# design.net
KiCad netlist of a schematic drawn in Altium Designer
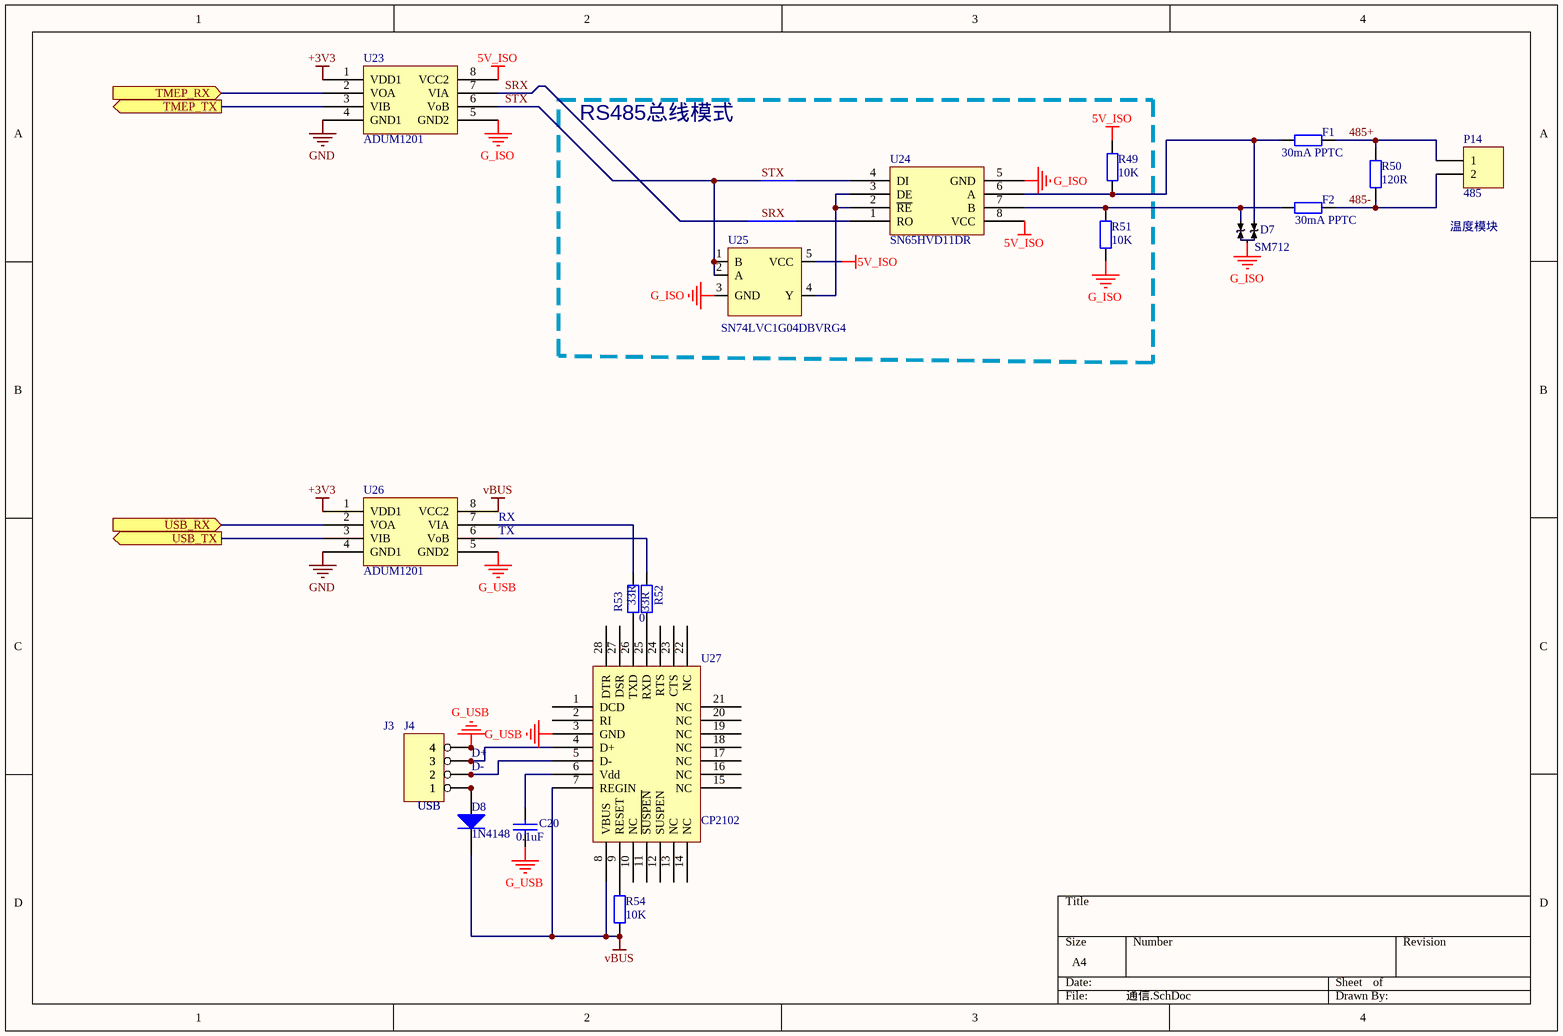
[diagram p0: 通信.SchDoc]

(export (version "E")
  (design (tool "Eeschema 10.0.6"))
  (components
    (comp (ref "C20")
      (value "0.1uF")
      (footprint "1608C")
      (description "Capacitor")
      (libsource (lib "*") (part "CAP"))
    )
    (comp (ref "D7") (value "SM712") (footprint "sot-23") (libsource (lib "Schlib1") (part "NUP2105L-D")))
    (comp (ref "D8")
      (value "1N4148")
      (footprint "SOD-123")
      (description "Default Diode")
      (fields (field (name "PUBLISHER") "Altium Limited"))
      (libsource (lib "*") (part "Diode"))
    )
    (comp (ref "F1")
      (value "30mA PPTC")
      (footprint "1608")
      (description "Resistor")
      (fields (field (name "PUBLISHER") "Altium Limited"))
      (libsource (lib "*") (part "Res2"))
    )
    (comp (ref "F2")
      (value "30mA PPTC")
      (footprint "1608")
      (description "Resistor")
      (fields (field (name "PUBLISHER") "Altium Limited"))
      (libsource (lib "*") (part "Res2"))
    )
    (comp (ref "J3")
      (value "USB")
      (footprint "ch2.5/4")
      (description "4 Pin Header")
      (libsource (lib "*") (part "4 HEADER"))
    )
    (comp (ref "J4")
      (value "USB")
      (footprint "USB-A-M")
      (description "4 Pin Header")
      (libsource (lib "*") (part "4 HEADER"))
    )
    (comp (ref "P14")
      (value "485")
      (footprint "5264-2")
      (description "Header, 2-Pin")
      (fields (field (name "PUBLISHER") "Altium Limited"))
      (libsource (lib "Miscellaneous Connectors") (part "Header 2"))
    )
    (comp (ref "R49")
      (value "10K")
      (footprint "1608")
      (description "Resistor")
      (fields (field (name "PUBLISHER") "Altium Limited"))
      (libsource (lib "") (part "Res2_1"))
    )
    (comp (ref "R50")
      (value "120R")
      (footprint "1608")
      (description "Resistor")
      (fields (field (name "PUBLISHER") "Altium Limited"))
      (libsource (lib "") (part "Res2_2"))
    )
    (comp (ref "R51")
      (value "10K")
      (footprint "1608")
      (description "Resistor")
      (fields (field (name "PUBLISHER") "Altium Limited"))
      (libsource (lib "") (part "Res2_2"))
    )
    (comp (ref "R52")
      (value "33R")
      (footprint "1608")
      (description "Resistor")
      (fields (field (name "PUBLISHER") "Altium Limited"))
      (libsource (lib "") (part "Res2_2"))
    )
    (comp (ref "R53")
      (value "33R")
      (footprint "1608")
      (description "Resistor")
      (fields (field (name "ALTIUM_VALUE") "0") (field (name "PUBLISHER") "Altium Limited"))
      (libsource (lib "") (part "Res2_2"))
    )
    (comp (ref "R54")
      (value "10K")
      (footprint "1608")
      (description "Resistor")
      (fields (field (name "PUBLISHER") "Altium Limited"))
      (libsource (lib "") (part "Res2_1"))
    )
    (comp (ref "U23") (value "ADUM1201") (footprint "so8") (libsource (lib "*") (part "max485")))
    (comp (ref "U24") (value "SN65HVD11DR") (footprint "so8") (libsource (lib "") (part "max485_1")))
    (comp (ref "U25")
      (value "SN74LVC1G04DBVRG4")
      (footprint "sot-23-5")
      (libsource (lib "Schlib1") (part "LMV321"))
    )
    (comp (ref "U26") (value "ADUM1201") (footprint "so8") (libsource (lib "*") (part "max485")))
    (comp (ref "U27") (value "CP2102") (footprint "QFN-28") (libsource (lib "*") (part "Component_1")))
  )
  (nets
    (net (code "1") (name "+3V3") (class "Default")
      (node (ref "U23") (pin "1") (pinfunction "VDD1_1") (pintype "passive"))
      (node (ref "U26") (pin "1") (pinfunction "VDD1_1") (pintype "passive"))
    )
    (net (code "2") (name "/485+") (class "Default")
      (node (ref "F1") (pin "1") (pinfunction "1_1") (pintype "passive"))
      (node (ref "P14") (pin "1") (pinfunction "1_1") (pintype "passive"))
      (node (ref "R50") (pin "2") (pinfunction "2_2") (pintype "passive"))
    )
    (net (code "3") (name "/485-") (class "Default")
      (node (ref "F2") (pin "1") (pinfunction "1_1") (pintype "passive"))
      (node (ref "P14") (pin "2") (pinfunction "2_2") (pintype "passive"))
      (node (ref "R50") (pin "1") (pinfunction "1_1") (pintype "passive"))
    )
    (net (code "4") (name "/SRX") (class "Default")
      (node (ref "U23") (pin "7") (pinfunction "VIA_7") (pintype "passive"))
      (node (ref "U24") (pin "1") (pinfunction "RO_1") (pintype "passive"))
    )
    (net (code "5") (name "/STX") (class "Default")
      (node (ref "U23") (pin "6") (pinfunction "VoB_6") (pintype "passive"))
      (node (ref "U24") (pin "4") (pinfunction "DI_4") (pintype "passive"))
      (node (ref "U25") (pin "1") (pinfunction "B_1") (pintype "passive"))
      (node (ref "U25") (pin "2") (pinfunction "A_2") (pintype "passive"))
    )
    (net (code "6") (name "/TMEP_RX") (class "Default")
      (node (ref "U23") (pin "2") (pinfunction "VOA_2") (pintype "passive"))
    )
    (net (code "7") (name "/TMEP_TX") (class "Default")
      (node (ref "U23") (pin "3") (pinfunction "VIB_3") (pintype "passive"))
    )
    (net (code "8") (name "/USB_RX") (class "Default")
      (node (ref "U26") (pin "2") (pinfunction "VOA_2") (pintype "passive"))
    )
    (net (code "9") (name "/USB_TX") (class "Default")
      (node (ref "U26") (pin "3") (pinfunction "VIB_3") (pintype "passive"))
    )
    (net (code "10") (name "5V_ISO") (class "Default")
      (node (ref "R49") (pin "1") (pinfunction "1_1") (pintype "passive"))
      (node (ref "U23") (pin "8") (pinfunction "VCC2_8") (pintype "passive"))
      (node (ref "U24") (pin "8") (pinfunction "VCC_8") (pintype "passive"))
      (node (ref "U25") (pin "5") (pinfunction "VCC_5") (pintype "passive"))
    )
    (net (code "11") (name "GND") (class "Default")
      (node (ref "U23") (pin "4") (pinfunction "GND1_4") (pintype "passive"))
      (node (ref "U26") (pin "4") (pinfunction "GND1_4") (pintype "passive"))
    )
    (net (code "12") (name "G_ISO") (class "Default")
      (node (ref "D7") (pin "3") (pinfunction "COM_3") (pintype "passive"))
      (node (ref "R51") (pin "1") (pinfunction "1_1") (pintype "passive"))
      (node (ref "U23") (pin "5") (pinfunction "GND2_5") (pintype "passive"))
      (node (ref "U24") (pin "5") (pinfunction "GND_5") (pintype "passive"))
      (node (ref "U25") (pin "3") (pinfunction "GND_3") (pintype "passive"))
    )
    (net (code "13") (name "G_USB") (class "Default")
      (node (ref "C20") (pin "2") (pinfunction "2_2") (pintype "passive"))
      (node (ref "J3") (pin "4") (pinfunction "4_4") (pintype "passive"))
      (node (ref "J4") (pin "4") (pinfunction "4_4") (pintype "passive"))
      (node (ref "U26") (pin "5") (pinfunction "GND2_5") (pintype "passive"))
      (node (ref "U27") (pin "3") (pinfunction "GND_3") (pintype "passive"))
    )
    (net (code "14") (name "Net-(D7-Blue)") (class "Default")
      (node (ref "D7") (pin "2") (pinfunction "Blue_2") (pintype "passive"))
      (node (ref "F1") (pin "2") (pinfunction "2_2") (pintype "passive"))
      (node (ref "R49") (pin "2") (pinfunction "2_2") (pintype "passive"))
      (node (ref "U24") (pin "6") (pinfunction "A_6") (pintype "passive"))
    )
    (net (code "15") (name "Net-(D7-Red)") (class "Default")
      (node (ref "D7") (pin "1") (pinfunction "Red_1") (pintype "passive"))
      (node (ref "F2") (pin "2") (pinfunction "2_2") (pintype "passive"))
      (node (ref "R51") (pin "2") (pinfunction "2_2") (pintype "passive"))
      (node (ref "U24") (pin "7") (pinfunction "B_7") (pintype "passive"))
    )
    (net (code "16") (name "Net-(D8-A)") (class "Default")
      (node (ref "D8") (pin "1") (pinfunction "A_1") (pintype "passive"))
      (node (ref "J3") (pin "1") (pinfunction "1_1") (pintype "passive"))
      (node (ref "J4") (pin "1") (pinfunction "1_1") (pintype "passive"))
    )
    (net (code "17") (name "Net-(U24-DE)") (class "Default")
      (node (ref "U24") (pin "2") (pinfunction "~{RE}_2") (pintype "passive"))
      (node (ref "U24") (pin "3") (pinfunction "DE_3") (pintype "passive"))
      (node (ref "U25") (pin "4") (pinfunction "Y_4") (pintype "passive"))
    )
    (net (code "18") (name "Net-(U26-VIA)") (class "Default")
      (node (ref "R53") (pin "2") (pinfunction "2_2") (pintype "passive"))
      (node (ref "U26") (pin "7") (pinfunction "VIA_7") (pintype "passive"))
    )
    (net (code "19") (name "Net-(U26-VoB)") (class "Default")
      (node (ref "R52") (pin "2") (pinfunction "2_2") (pintype "passive"))
      (node (ref "U26") (pin "6") (pinfunction "VoB_6") (pintype "passive"))
    )
    (net (code "20") (name "Net-(U27-D+)") (class "Default")
      (node (ref "J3") (pin "3") (pinfunction "3_3") (pintype "passive"))
      (node (ref "J4") (pin "3") (pinfunction "3_3") (pintype "passive"))
      (node (ref "U27") (pin "4") (pinfunction "D+_4") (pintype "passive"))
    )
    (net (code "21") (name "Net-(U27-D-)") (class "Default")
      (node (ref "J3") (pin "2") (pinfunction "2_2") (pintype "passive"))
      (node (ref "J4") (pin "2") (pinfunction "2_2") (pintype "passive"))
      (node (ref "U27") (pin "5") (pinfunction "D-_5") (pintype "passive"))
    )
    (net (code "22") (name "Net-(U27-RESET)") (class "Default")
      (node (ref "R54") (pin "1") (pinfunction "1_1") (pintype "passive"))
      (node (ref "U27") (pin "9") (pinfunction "RESET_9") (pintype "passive"))
    )
    (net (code "23") (name "Net-(U27-RXD)") (class "Default")
      (node (ref "R52") (pin "1") (pinfunction "1_1") (pintype "passive"))
      (node (ref "U27") (pin "25") (pinfunction "RXD_25") (pintype "passive"))
    )
    (net (code "24") (name "Net-(U27-TXD)") (class "Default")
      (node (ref "R53") (pin "1") (pinfunction "1_1") (pintype "passive"))
      (node (ref "U27") (pin "26") (pinfunction "TXD_26") (pintype "passive"))
    )
    (net (code "25") (name "Net-(U27-Vdd)") (class "Default")
      (node (ref "C20") (pin "1") (pinfunction "1_1") (pintype "passive"))
      (node (ref "U27") (pin "6") (pinfunction "Vdd_6") (pintype "passive"))
    )
    (net (code "26") (name "unconnected-(U27-CTS-Pad23)") (class "Default")
      (node (ref "U27") (pin "23") (pinfunction "CTS_23") (pintype "passive"))
    )
    (net (code "27") (name "unconnected-(U27-DCD-Pad1)") (class "Default")
      (node (ref "U27") (pin "1") (pinfunction "DCD_1") (pintype "passive"))
    )
    (net (code "28") (name "unconnected-(U27-DSR-Pad27)") (class "Default")
      (node (ref "U27") (pin "27") (pinfunction "DSR_27") (pintype "passive"))
    )
    (net (code "29") (name "unconnected-(U27-DTR-Pad28)") (class "Default")
      (node (ref "U27") (pin "28") (pinfunction "DTR_28") (pintype "passive"))
    )
    (net (code "30") (name "unconnected-(U27-NC-Pad10)") (class "Default")
      (node (ref "U27") (pin "10") (pinfunction "NC_10") (pintype "passive"))
    )
    (net (code "31") (name "unconnected-(U27-NC-Pad13)") (class "Default")
      (node (ref "U27") (pin "13") (pinfunction "NC_13") (pintype "passive"))
    )
    (net (code "32") (name "unconnected-(U27-NC-Pad14)") (class "Default")
      (node (ref "U27") (pin "14") (pinfunction "NC_14") (pintype "passive"))
    )
    (net (code "33") (name "unconnected-(U27-NC-Pad15)") (class "Default")
      (node (ref "U27") (pin "15") (pinfunction "NC_15") (pintype "passive"))
    )
    (net (code "34") (name "unconnected-(U27-NC-Pad16)") (class "Default")
      (node (ref "U27") (pin "16") (pinfunction "NC_16") (pintype "passive"))
    )
    (net (code "35") (name "unconnected-(U27-NC-Pad17)") (class "Default")
      (node (ref "U27") (pin "17") (pinfunction "NC_17") (pintype "passive"))
    )
    (net (code "36") (name "unconnected-(U27-NC-Pad18)") (class "Default")
      (node (ref "U27") (pin "18") (pinfunction "NC_18") (pintype "passive"))
    )
    (net (code "37") (name "unconnected-(U27-NC-Pad19)") (class "Default")
      (node (ref "U27") (pin "19") (pinfunction "NC_19") (pintype "passive"))
    )
    (net (code "38") (name "unconnected-(U27-NC-Pad20)") (class "Default")
      (node (ref "U27") (pin "20") (pinfunction "NC_20") (pintype "passive"))
    )
    (net (code "39") (name "unconnected-(U27-NC-Pad21)") (class "Default")
      (node (ref "U27") (pin "21") (pinfunction "NC_21") (pintype "passive"))
    )
    (net (code "40") (name "unconnected-(U27-NC-Pad22)") (class "Default")
      (node (ref "U27") (pin "22") (pinfunction "NC_22") (pintype "passive"))
    )
    (net (code "41") (name "unconnected-(U27-RI-Pad2)") (class "Default")
      (node (ref "U27") (pin "2") (pinfunction "RI_2") (pintype "passive"))
    )
    (net (code "42") (name "unconnected-(U27-RTS-Pad24)") (class "Default")
      (node (ref "U27") (pin "24") (pinfunction "RTS_24") (pintype "passive"))
    )
    (net (code "43") (name "unconnected-(U27-SUSPEN-Pad12)") (class "Default")
      (node (ref "U27") (pin "12") (pinfunction "SUSPEN_12") (pintype "passive"))
    )
    (net (code "44") (name "unconnected-(U27-~{SUSPEN}-Pad11)") (class "Default")
      (node (ref "U27") (pin "11") (pinfunction "~{SUSPEN}_11") (pintype "passive"))
    )
    (net (code "45") (name "vBUS") (class "Default")
      (node (ref "D8") (pin "2") (pinfunction "K_2") (pintype "passive"))
      (node (ref "R54") (pin "2") (pinfunction "2_2") (pintype "passive"))
      (node (ref "U26") (pin "8") (pinfunction "VCC2_8") (pintype "passive"))
      (node (ref "U27") (pin "7") (pinfunction "REGIN_7") (pintype "passive"))
      (node (ref "U27") (pin "8") (pinfunction "VBUS_8") (pintype "passive"))
    )
  )
)
